# schema.net
KiCad netlist of a schematic drawn in Altium Designer
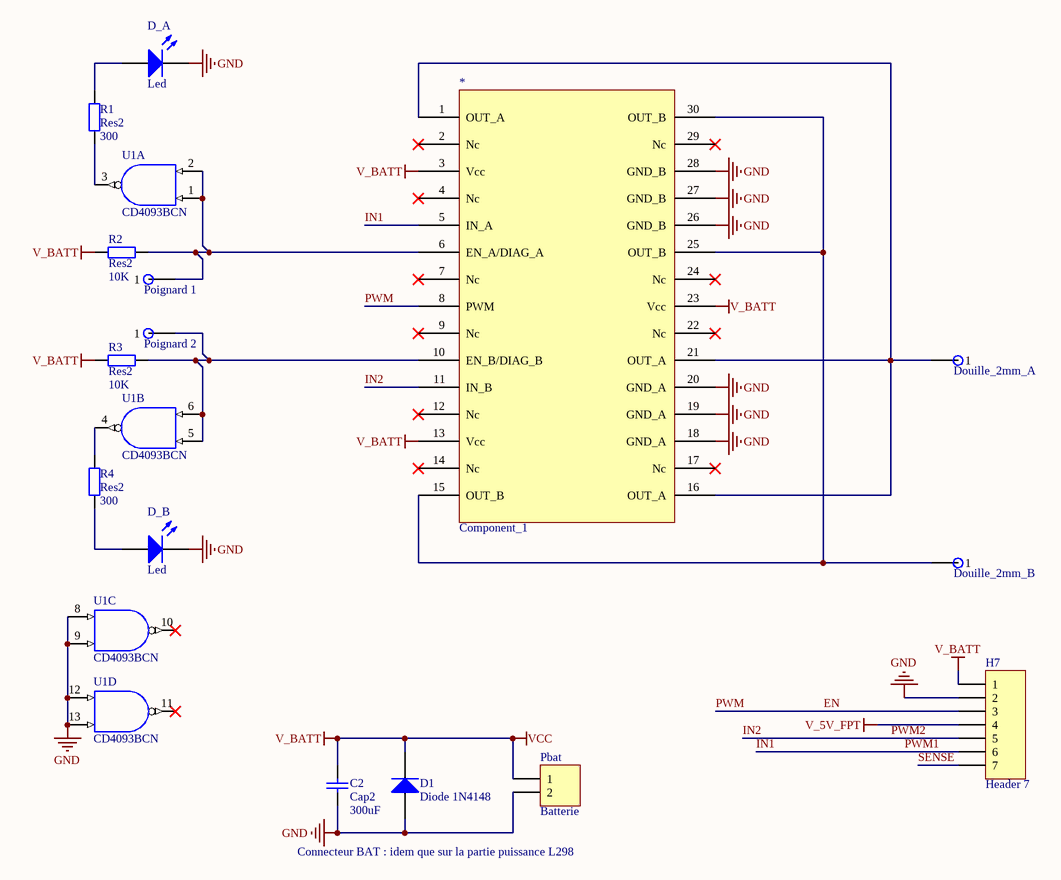
[diagram p0: schema.SchDoc]

(export (version "E")
  (design (tool "Eeschema 10.0.6"))
  (components
    (comp (ref "*")
      (value "Component_1")
      (footprint "MultiPowerSO-30")
      (libsource (lib "VNH3SP30-E") (part "Component_1"))
    )
    (comp (ref "C2")
      (value "Cap2")
      (footprint "CAPA2")
      (description "Capacitor")
      (fields (field (name "ALTIUM_VALUE") "300uF") (field (name "PUBLISHER") "Altium Limited"))
      (libsource (lib "LIBRAIRIE_INTEGREE_PHELMA1") (part "Cap2"))
    )
    (comp (ref "D1")
      (value "Diode 1N4148")
      (footprint "Ddiode")
      (description "High Conductance Fast Diode")
      (fields (field (name "PUBLISHER") "Altium Limited"))
      (libsource (lib "LIBRAIRIE_INTEGREE_PHELMA1") (part "Diode 1N4148"))
    )
    (comp (ref "Douille_2mm_A")
      (value "douille_2mm")
      (footprint "Douille-2mm")
      (description "1-Pin")
      (fields (field (name "PUBLISHER") "Altium Limited"))
      (libsource (lib "INTEGRATED_LIBRARY1_CONNECTEURS") (part "douille_2mm"))
    )
    (comp (ref "Douille_2mm_B")
      (value "douille_2mm")
      (footprint "Douille-2mm")
      (description "1-Pin")
      (fields (field (name "PUBLISHER") "Altium Limited"))
      (libsource (lib "INTEGRATED_LIBRARY1_CONNECTEURS") (part "douille_2mm"))
    )
    (comp (ref "D_A")
      (value "Led")
      (footprint "LED")
      (description "LED")
      (fields (field (name "PUBLISHER") "Altium Limited"))
      (libsource (lib "LIBRAIRIE_INTEGREE_PHELMA1") (part "Led"))
    )
    (comp (ref "D_B")
      (value "Led")
      (footprint "LED")
      (description "LED")
      (fields (field (name "PUBLISHER") "Altium Limited"))
      (libsource (lib "LIBRAIRIE_INTEGREE_PHELMA1") (part "Led"))
    )
    (comp (ref "H7")
      (value "Header 7")
      (footprint "HDR1X7")
      (description "Header, 7-Pin")
      (fields (field (name "PUBLISHER") "Altium Limited"))
      (libsource (lib "Miscellaneous Connectors") (part "Header 7"))
    )
    (comp (ref "Pbat")
      (value "Batterie")
      (footprint "Bornier_2")
      (description "Header, 2-Pin")
      (fields (field (name "PUBLISHER") "Altium Limited"))
      (libsource (lib "INTEGRATED_LIBRARY1_CONNECTEURS") (part "Bornier_2"))
    )
    (comp (ref "Poignard 1")
      (value "Poignard")
      (footprint "Poignard")
      (fields (field (name "PUBLISHER") "Altium Limited"))
      (libsource (lib "INTEGRATED_LIBRARY1_CONNECTEURS") (part "Poignard"))
    )
    (comp (ref "Poignard 2")
      (value "Poignard")
      (footprint "Poignard")
      (fields (field (name "PUBLISHER") "Altium Limited"))
      (libsource (lib "INTEGRATED_LIBRARY1_CONNECTEURS") (part "Poignard"))
    )
    (comp (ref "R1")
      (value "Res2")
      (footprint "res5_1/4W")
      (description "Resistor")
      (fields (field (name "ALTIUM_VALUE") "300") (field (name "PUBLISHER") "Altium Limited"))
      (libsource (lib "LIBRAIRIE_INTEGREE_PHELMA1") (part "Res2"))
    )
    (comp (ref "R2")
      (value "Res2")
      (footprint "res5_1/4W")
      (description "Resistor")
      (fields (field (name "ALTIUM_VALUE") "10K") (field (name "PUBLISHER") "Altium Limited"))
      (libsource (lib "") (part "Res2_1"))
    )
    (comp (ref "R3")
      (value "Res2")
      (footprint "res5_1/4W")
      (description "Resistor")
      (fields (field (name "ALTIUM_VALUE") "10K") (field (name "PUBLISHER") "Altium Limited"))
      (libsource (lib "") (part "Res2_1"))
    )
    (comp (ref "R4")
      (value "Res2")
      (footprint "res5_1/4W")
      (description "Resistor")
      (fields (field (name "ALTIUM_VALUE") "300") (field (name "PUBLISHER") "Altium Limited"))
      (libsource (lib "LIBRAIRIE_INTEGREE_PHELMA1") (part "Res2"))
    )
    (comp (ref "U1")
      (value "CD4093BCN")
      (footprint "DIP14")
      (description "Quad 2-Input NAND Schmitt Trigger")
      (fields (field (name "PUBLISHER") "Altium Limited"))
      (libsource (lib "LIBRAIRIE_INTEGREE_PHELMA1") (part "CD4093BCN"))
    )
  )
  (nets
    (net (code "1") (name "/EN") (class "Default")
      (node (ref "*") (pin "8") (pinfunction "PWM_8") (pintype "passive"))
      (node (ref "H7") (pin "3") (pinfunction "3_3") (pintype "passive"))
    )
    (net (code "2") (name "/IN1") (class "Default")
      (node (ref "*") (pin "5") (pinfunction "IN_A_5") (pintype "passive"))
      (node (ref "H7") (pin "6") (pinfunction "6_6") (pintype "passive"))
    )
    (net (code "3") (name "/IN2") (class "Default")
      (node (ref "*") (pin "11") (pinfunction "IN_B_11") (pintype "passive"))
      (node (ref "H7") (pin "5") (pinfunction "5_5") (pintype "passive"))
    )
    (net (code "4") (name "/SENSE") (class "Default")
      (node (ref "H7") (pin "7") (pinfunction "7_7") (pintype "passive"))
    )
    (net (code "5") (name "GND") (class "Default")
      (node (ref "*") (pin "18") (pinfunction "GND_A_18") (pintype "passive"))
      (node (ref "*") (pin "19") (pinfunction "GND_A_19") (pintype "passive"))
      (node (ref "*") (pin "20") (pinfunction "GND_A_20") (pintype "passive"))
      (node (ref "*") (pin "26") (pinfunction "GND_B_26") (pintype "passive"))
      (node (ref "*") (pin "27") (pinfunction "GND_B_27") (pintype "passive"))
      (node (ref "*") (pin "28") (pinfunction "GND_B_28") (pintype "passive"))
      (node (ref "C2") (pin "1") (pinfunction "1_1") (pintype "passive"))
      (node (ref "D1") (pin "1") (pinfunction "A_1") (pintype "passive"))
      (node (ref "D_A") (pin "2") (pinfunction "K_2") (pintype "passive"))
      (node (ref "D_B") (pin "2") (pinfunction "K_2") (pintype "passive"))
      (node (ref "H7") (pin "2") (pinfunction "2_2") (pintype "passive"))
      (node (ref "Pbat") (pin "2") (pinfunction "2_2") (pintype "passive"))
      (node (ref "U1") (pin "12") (pinfunction "G_12") (pintype "input"))
      (node (ref "U1") (pin "13") (pinfunction "H_13") (pintype "input"))
      (node (ref "U1") (pin "7") (pinfunction "GND_7") (pintype "power_in"))
      (node (ref "U1") (pin "8") (pinfunction "E_8") (pintype "input"))
      (node (ref "U1") (pin "9") (pinfunction "F_9") (pintype "input"))
    )
    (net (code "6") (name "Net-(*-EN_A{slash}DIAG_A)") (class "Default")
      (node (ref "*") (pin "6") (pinfunction "EN_A/DIAG_A_6") (pintype "passive"))
      (node (ref "Poignard 1") (pin "1") (pinfunction "1_1") (pintype "passive"))
      (node (ref "R2") (pin "2") (pinfunction "2_2") (pintype "passive"))
      (node (ref "U1") (pin "1") (pinfunction "A_1") (pintype "input"))
      (node (ref "U1") (pin "2") (pinfunction "B_2") (pintype "input"))
    )
    (net (code "7") (name "Net-(*-EN_B{slash}DIAG_B)") (class "Default")
      (node (ref "*") (pin "10") (pinfunction "EN_B/DIAG_B_10") (pintype "passive"))
      (node (ref "Poignard 2") (pin "1") (pinfunction "1_1") (pintype "passive"))
      (node (ref "R3") (pin "2") (pinfunction "2_2") (pintype "passive"))
      (node (ref "U1") (pin "5") (pinfunction "C_5") (pintype "input"))
      (node (ref "U1") (pin "6") (pinfunction "D_6") (pintype "input"))
    )
    (net (code "8") (name "Net-(*-OUT_A-Pad1)") (class "Default")
      (node (ref "*") (pin "1") (pinfunction "OUT_A_1") (pintype "passive"))
      (node (ref "*") (pin "16") (pinfunction "OUT_A_16") (pintype "passive"))
      (node (ref "*") (pin "21") (pinfunction "OUT_A_21") (pintype "passive"))
      (node (ref "Douille_2mm_A") (pin "1") (pinfunction "1_1") (pintype "passive"))
    )
    (net (code "9") (name "Net-(*-OUT_B-Pad15)") (class "Default")
      (node (ref "*") (pin "15") (pinfunction "OUT_B_15") (pintype "passive"))
      (node (ref "*") (pin "25") (pinfunction "OUT_B_25") (pintype "passive"))
      (node (ref "*") (pin "30") (pinfunction "OUT_B_30") (pintype "passive"))
      (node (ref "Douille_2mm_B") (pin "1") (pinfunction "1_1") (pintype "passive"))
    )
    (net (code "10") (name "Net-(D_A-A)") (class "Default")
      (node (ref "D_A") (pin "1") (pinfunction "A_1") (pintype "passive"))
      (node (ref "R1") (pin "2") (pinfunction "2_2") (pintype "passive"))
    )
    (net (code "11") (name "Net-(D_B-A)") (class "Default")
      (node (ref "D_B") (pin "1") (pinfunction "A_1") (pintype "passive"))
      (node (ref "R4") (pin "1") (pinfunction "1_1") (pintype "passive"))
    )
    (net (code "12") (name "Net-(U1A-J)") (class "Default")
      (node (ref "R1") (pin "1") (pinfunction "1_1") (pintype "passive"))
      (node (ref "U1") (pin "3") (pinfunction "J_3") (pintype "output"))
    )
    (net (code "13") (name "Net-(U1B-K)") (class "Default")
      (node (ref "R4") (pin "2") (pinfunction "2_2") (pintype "passive"))
      (node (ref "U1") (pin "4") (pinfunction "K_4") (pintype "output"))
    )
    (net (code "14") (name "VCC") (class "Default")
      (node (ref "*") (pin "13") (pinfunction "Vcc_13") (pintype "passive"))
      (node (ref "*") (pin "23") (pinfunction "Vcc_23") (pintype "passive"))
      (node (ref "*") (pin "3") (pinfunction "Vcc_3") (pintype "passive"))
      (node (ref "C2") (pin "2") (pinfunction "2_2") (pintype "passive"))
      (node (ref "D1") (pin "2") (pinfunction "K_2") (pintype "passive"))
      (node (ref "H7") (pin "1") (pinfunction "1_1") (pintype "passive"))
      (node (ref "Pbat") (pin "1") (pinfunction "1_1") (pintype "passive"))
      (node (ref "R2") (pin "1") (pinfunction "1_1") (pintype "passive"))
      (node (ref "R3") (pin "1") (pinfunction "1_1") (pintype "passive"))
      (node (ref "U1") (pin "14") (pinfunction "VCC_14") (pintype "power_in"))
    )
    (net (code "15") (name "V_5V_FPT") (class "Default")
      (node (ref "H7") (pin "4") (pinfunction "4_4") (pintype "passive"))
    )
    (net (code "16") (name "unconnected-(*-Nc-Pad2)") (class "Default")
      (node (ref "*") (pin "2") (pinfunction "Nc_2") (pintype "passive+no_connect"))
    )
    (net (code "17") (name "unconnected-(*-Nc-Pad4)") (class "Default")
      (node (ref "*") (pin "4") (pinfunction "Nc_4") (pintype "passive+no_connect"))
    )
    (net (code "18") (name "unconnected-(*-Nc-Pad7)") (class "Default")
      (node (ref "*") (pin "7") (pinfunction "Nc_7") (pintype "passive+no_connect"))
    )
    (net (code "19") (name "unconnected-(*-Nc-Pad9)") (class "Default")
      (node (ref "*") (pin "9") (pinfunction "Nc_9") (pintype "passive+no_connect"))
    )
    (net (code "20") (name "unconnected-(*-Nc-Pad12)") (class "Default")
      (node (ref "*") (pin "12") (pinfunction "Nc_12") (pintype "passive+no_connect"))
    )
    (net (code "21") (name "unconnected-(*-Nc-Pad14)") (class "Default")
      (node (ref "*") (pin "14") (pinfunction "Nc_14") (pintype "passive+no_connect"))
    )
    (net (code "22") (name "unconnected-(*-Nc-Pad17)") (class "Default")
      (node (ref "*") (pin "17") (pinfunction "Nc_17") (pintype "passive+no_connect"))
    )
    (net (code "23") (name "unconnected-(*-Nc-Pad22)") (class "Default")
      (node (ref "*") (pin "22") (pinfunction "Nc_22") (pintype "passive+no_connect"))
    )
    (net (code "24") (name "unconnected-(*-Nc-Pad24)") (class "Default")
      (node (ref "*") (pin "24") (pinfunction "Nc_24") (pintype "passive+no_connect"))
    )
    (net (code "25") (name "unconnected-(*-Nc-Pad29)") (class "Default")
      (node (ref "*") (pin "29") (pinfunction "Nc_29") (pintype "passive+no_connect"))
    )
    (net (code "26") (name "unconnected-(U1C-L-Pad10)") (class "Default")
      (node (ref "U1") (pin "10") (pinfunction "L_10") (pintype "output+no_connect"))
    )
    (net (code "27") (name "unconnected-(U1D-M-Pad11)") (class "Default")
      (node (ref "U1") (pin "11") (pinfunction "M_11") (pintype "output+no_connect"))
    )
  )
)
